# phasor.net
KiCad netlist of a schematic drawn in EAGLE
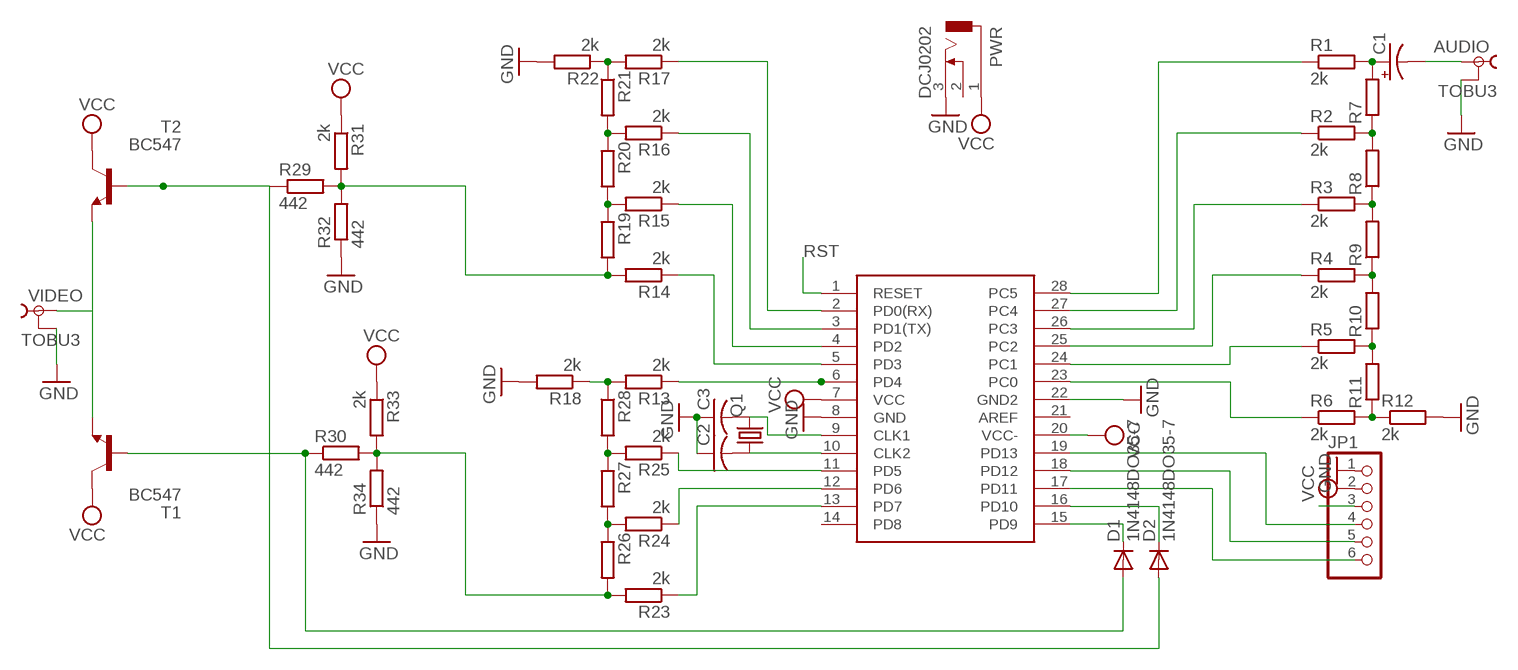
[diagram p0: schematic, sheet 1]

(export (version "E")
  (design (tool "Eeschema 10.0.6"))
  (components
    (comp (ref "AUDIO")
      (value "TOBU3")
      (footprint "eagle-import:TOBU3")
      (fields (field (name "MF") "FARNELL") (field (name "MPN") "TOBU 3"))
      (libsource (lib "eagle-import") (part "TOBU3"))
    )
    (comp (ref "C1")
      (value "CPOL-USB45181A")
      (footprint "eagle-import:B45181A")
      (libsource (lib "eagle-import") (part "CPOL-USB45181A"))
    )
    (comp (ref "C2")
      (value "C-US025-024X044")
      (footprint "eagle-import:C025-024X044")
      (libsource (lib "eagle-import") (part "C-US025-024X044"))
    )
    (comp (ref "C3")
      (value "C-US025-024X044")
      (footprint "eagle-import:C025-024X044")
      (libsource (lib "eagle-import") (part "C-US025-024X044"))
    )
    (comp (ref "D1")
      (value "1N4148DO35-7")
      (footprint "eagle-import:DO35-7")
      (libsource (lib "eagle-import") (part "1N4148DO35-7"))
    )
    (comp (ref "D2")
      (value "1N4148DO35-7")
      (footprint "eagle-import:DO35-7")
      (libsource (lib "eagle-import") (part "1N4148DO35-7"))
    )
    (comp (ref "JP1")
      (value "PINHD-1X6")
      (footprint "eagle-import:1X06")
      (libsource (lib "eagle-import") (part "PINHD-1X6"))
    )
    (comp (ref "PWR")
      (value "DCJ0202")
      (footprint "eagle-import:DCJ0202")
      (libsource (lib "eagle-import") (part "DCJ0202"))
    )
    (comp (ref "Q1")
      (value "CRYSTALHC49U70")
      (footprint "eagle-import:HC49U70")
      (libsource (lib "eagle-import") (part "CRYSTALHC49U70"))
    )
    (comp (ref "R1")
      (value "2k")
      (footprint "eagle-import:0207_10")
      (libsource (lib "eagle-import") (part "R-EU_0207/10"))
    )
    (comp (ref "R2")
      (value "2k")
      (footprint "eagle-import:0207_10")
      (libsource (lib "eagle-import") (part "R-EU_0207/10"))
    )
    (comp (ref "R3")
      (value "2k")
      (footprint "eagle-import:0207_10")
      (libsource (lib "eagle-import") (part "R-EU_0207/10"))
    )
    (comp (ref "R4")
      (value "2k")
      (footprint "eagle-import:0207_10")
      (libsource (lib "eagle-import") (part "R-EU_0207/10"))
    )
    (comp (ref "R5")
      (value "2k")
      (footprint "eagle-import:0207_10")
      (libsource (lib "eagle-import") (part "R-EU_0207/10"))
    )
    (comp (ref "R6")
      (value "2k")
      (footprint "eagle-import:0207_10")
      (libsource (lib "eagle-import") (part "R-EU_0207/10"))
    )
    (comp (ref "R7")
      (value "R-EU_0204/2V")
      (footprint "eagle-import:0204V")
      (libsource (lib "eagle-import") (part "R-EU_0204/2V"))
    )
    (comp (ref "R8")
      (value "R-EU_0204/2V")
      (footprint "eagle-import:0204V")
      (libsource (lib "eagle-import") (part "R-EU_0204/2V"))
    )
    (comp (ref "R9")
      (value "R-EU_0204/2V")
      (footprint "eagle-import:0204V")
      (libsource (lib "eagle-import") (part "R-EU_0204/2V"))
    )
    (comp (ref "R10")
      (value "R-EU_0204/2V")
      (footprint "eagle-import:0204V")
      (libsource (lib "eagle-import") (part "R-EU_0204/2V"))
    )
    (comp (ref "R11")
      (value "R-EU_0204/2V")
      (footprint "eagle-import:0204V")
      (libsource (lib "eagle-import") (part "R-EU_0204/2V"))
    )
    (comp (ref "R12")
      (value "2k")
      (footprint "eagle-import:0207_10")
      (libsource (lib "eagle-import") (part "R-EU_0207/10"))
    )
    (comp (ref "R13")
      (value "2k")
      (footprint "eagle-import:0207_10")
      (libsource (lib "eagle-import") (part "R-EU_0207/10"))
    )
    (comp (ref "R14")
      (value "2k")
      (footprint "eagle-import:0207_10")
      (libsource (lib "eagle-import") (part "R-EU_0207/10"))
    )
    (comp (ref "R15")
      (value "2k")
      (footprint "eagle-import:0207_10")
      (libsource (lib "eagle-import") (part "R-EU_0207/10"))
    )
    (comp (ref "R16")
      (value "2k")
      (footprint "eagle-import:0207_10")
      (libsource (lib "eagle-import") (part "R-EU_0207/10"))
    )
    (comp (ref "R17")
      (value "2k")
      (footprint "eagle-import:0207_10")
      (libsource (lib "eagle-import") (part "R-EU_0207/10"))
    )
    (comp (ref "R18")
      (value "2k")
      (footprint "eagle-import:0207_10")
      (libsource (lib "eagle-import") (part "R-EU_0207/10"))
    )
    (comp (ref "R19")
      (value "R-EU_0204/2V")
      (footprint "eagle-import:0204V")
      (libsource (lib "eagle-import") (part "R-EU_0204/2V"))
    )
    (comp (ref "R20")
      (value "R-EU_0204/2V")
      (footprint "eagle-import:0204V")
      (libsource (lib "eagle-import") (part "R-EU_0204/2V"))
    )
    (comp (ref "R21")
      (value "R-EU_0204/2V")
      (footprint "eagle-import:0204V")
      (libsource (lib "eagle-import") (part "R-EU_0204/2V"))
    )
    (comp (ref "R22")
      (value "2k")
      (footprint "eagle-import:0207_10")
      (libsource (lib "eagle-import") (part "R-EU_0207/10"))
    )
    (comp (ref "R23")
      (value "2k")
      (footprint "eagle-import:0207_10")
      (libsource (lib "eagle-import") (part "R-EU_0207/10"))
    )
    (comp (ref "R24")
      (value "2k")
      (footprint "eagle-import:0207_10")
      (libsource (lib "eagle-import") (part "R-EU_0207/10"))
    )
    (comp (ref "R25")
      (value "2k")
      (footprint "eagle-import:0207_10")
      (libsource (lib "eagle-import") (part "R-EU_0207/10"))
    )
    (comp (ref "R26")
      (value "R-EU_0204/2V")
      (footprint "eagle-import:0204V")
      (libsource (lib "eagle-import") (part "R-EU_0204/2V"))
    )
    (comp (ref "R27")
      (value "R-EU_0204/2V")
      (footprint "eagle-import:0204V")
      (libsource (lib "eagle-import") (part "R-EU_0204/2V"))
    )
    (comp (ref "R28")
      (value "R-EU_0204/2V")
      (footprint "eagle-import:0204V")
      (libsource (lib "eagle-import") (part "R-EU_0204/2V"))
    )
    (comp (ref "R29")
      (value "442")
      (footprint "eagle-import:0204_5")
      (libsource (lib "eagle-import") (part "R-EU_0204/5"))
    )
    (comp (ref "R30")
      (value "442")
      (footprint "eagle-import:0204V")
      (libsource (lib "eagle-import") (part "R-EU_0204/2V"))
    )
    (comp (ref "R31")
      (value "2k")
      (footprint "eagle-import:0207_10")
      (libsource (lib "eagle-import") (part "R-EU_0207/10"))
    )
    (comp (ref "R32")
      (value "442")
      (footprint "eagle-import:0204V")
      (libsource (lib "eagle-import") (part "R-EU_0204/2V"))
    )
    (comp (ref "R33")
      (value "2k")
      (footprint "eagle-import:0207_10")
      (libsource (lib "eagle-import") (part "R-EU_0207/10"))
    )
    (comp (ref "R34")
      (value "442")
      (footprint "eagle-import:0204V")
      (libsource (lib "eagle-import") (part "R-EU_0204/2V"))
    )
    (comp (ref "T1")
      (value "BC547")
      (footprint "eagle-import:TO92")
      (libsource (lib "eagle-import") (part "BC547"))
    )
    (comp (ref "T2")
      (value "BC547")
      (footprint "eagle-import:TO92")
      (libsource (lib "eagle-import") (part "BC547"))
    )
    (comp (ref "U$1")
      (value "328P")
      (footprint "eagle-import:DIL28-3")
      (libsource (lib "eagle-import") (part "328P"))
    )
    (comp (ref "VIDEO")
      (value "TOBU3")
      (footprint "eagle-import:TOBU3")
      (fields (field (name "MF") "FARNELL") (field (name "MPN") "TOBU 3"))
      (libsource (lib "eagle-import") (part "TOBU3"))
    )
  )
  (nets
    (net (code "1") (name "/RST") (class "Default")
      (node (ref "JP1") (pin "3") (pinfunction "3_3") (pintype "passive"))
      (node (ref "U$1") (pin "1") (pinfunction "RESET_1") (pintype "bidirectional"))
    )
    (net (code "2") (name "GND") (class "Default")
      (node (ref "AUDIO") (pin "2") (pinfunction "2_2") (pintype "passive"))
      (node (ref "AUDIO") (pin "2@1") (pinfunction "2_2@1") (pintype "passive"))
      (node (ref "AUDIO") (pin "2@2") (pinfunction "2_2@2") (pintype "passive"))
      (node (ref "C2") (pin "1") (pinfunction "1_1") (pintype "passive"))
      (node (ref "C3") (pin "1") (pinfunction "1_1") (pintype "passive"))
      (node (ref "JP1") (pin "1") (pinfunction "1_1") (pintype "passive"))
      (node (ref "PWR") (pin "3") (pinfunction "3_3") (pintype "passive"))
      (node (ref "R12") (pin "2") (pinfunction "2_2") (pintype "passive"))
      (node (ref "R18") (pin "2") (pinfunction "2_2") (pintype "passive"))
      (node (ref "R22") (pin "2") (pinfunction "2_2") (pintype "passive"))
      (node (ref "R32") (pin "1") (pinfunction "1_1") (pintype "passive"))
      (node (ref "R34") (pin "1") (pinfunction "1_1") (pintype "passive"))
      (node (ref "U$1") (pin "22") (pinfunction "GND2_22") (pintype "bidirectional"))
      (node (ref "U$1") (pin "8") (pinfunction "GND_8") (pintype "bidirectional"))
      (node (ref "VIDEO") (pin "2") (pinfunction "2_2") (pintype "passive"))
      (node (ref "VIDEO") (pin "2@1") (pinfunction "2_2@1") (pintype "passive"))
      (node (ref "VIDEO") (pin "2@2") (pinfunction "2_2@2") (pintype "passive"))
    )
    (net (code "3") (name "Net-(AUDIO-Pad1)") (class "Default")
      (node (ref "AUDIO") (pin "1") (pinfunction "1_1") (pintype "passive"))
      (node (ref "C1") (pin "-") (pinfunction "-_-") (pintype "passive"))
    )
    (net (code "4") (name "Net-(C1-Pad+)") (class "Default")
      (node (ref "C1") (pin "+") (pinfunction "+_+") (pintype "passive"))
      (node (ref "R1") (pin "2") (pinfunction "2_2") (pintype "passive"))
      (node (ref "R7") (pin "2") (pinfunction "2_2") (pintype "passive"))
    )
    (net (code "5") (name "Net-(R2-Pad2)") (class "Default")
      (node (ref "R2") (pin "2") (pinfunction "2_2") (pintype "passive"))
      (node (ref "R7") (pin "1") (pinfunction "1_1") (pintype "passive"))
      (node (ref "R8") (pin "2") (pinfunction "2_2") (pintype "passive"))
    )
    (net (code "6") (name "Net-(R3-Pad2)") (class "Default")
      (node (ref "R3") (pin "2") (pinfunction "2_2") (pintype "passive"))
      (node (ref "R8") (pin "1") (pinfunction "1_1") (pintype "passive"))
      (node (ref "R9") (pin "2") (pinfunction "2_2") (pintype "passive"))
    )
    (net (code "7") (name "Net-(R10-Pad1)") (class "Default")
      (node (ref "R10") (pin "1") (pinfunction "1_1") (pintype "passive"))
      (node (ref "R11") (pin "2") (pinfunction "2_2") (pintype "passive"))
      (node (ref "R5") (pin "2") (pinfunction "2_2") (pintype "passive"))
    )
    (net (code "8") (name "Net-(R10-Pad2)") (class "Default")
      (node (ref "R10") (pin "2") (pinfunction "2_2") (pintype "passive"))
      (node (ref "R4") (pin "2") (pinfunction "2_2") (pintype "passive"))
      (node (ref "R9") (pin "1") (pinfunction "1_1") (pintype "passive"))
    )
    (net (code "9") (name "Net-(R11-Pad1)") (class "Default")
      (node (ref "R11") (pin "1") (pinfunction "1_1") (pintype "passive"))
      (node (ref "R12") (pin "1") (pinfunction "1_1") (pintype "passive"))
      (node (ref "R6") (pin "2") (pinfunction "2_2") (pintype "passive"))
    )
    (net (code "10") (name "Net-(R13-Pad2)") (class "Default")
      (node (ref "R13") (pin "2") (pinfunction "2_2") (pintype "passive"))
      (node (ref "R18") (pin "1") (pinfunction "1_1") (pintype "passive"))
      (node (ref "R28") (pin "1") (pinfunction "1_1") (pintype "passive"))
    )
    (net (code "11") (name "Net-(R14-Pad2)") (class "Default")
      (node (ref "R14") (pin "2") (pinfunction "2_2") (pintype "passive"))
      (node (ref "R19") (pin "2") (pinfunction "2_2") (pintype "passive"))
      (node (ref "R29") (pin "2") (pinfunction "2_2") (pintype "passive"))
      (node (ref "R31") (pin "2") (pinfunction "2_2") (pintype "passive"))
      (node (ref "R32") (pin "2") (pinfunction "2_2") (pintype "passive"))
    )
    (net (code "12") (name "Net-(R15-Pad2)") (class "Default")
      (node (ref "R15") (pin "2") (pinfunction "2_2") (pintype "passive"))
      (node (ref "R19") (pin "1") (pinfunction "1_1") (pintype "passive"))
      (node (ref "R20") (pin "2") (pinfunction "2_2") (pintype "passive"))
    )
    (net (code "13") (name "Net-(R16-Pad2)") (class "Default")
      (node (ref "R16") (pin "2") (pinfunction "2_2") (pintype "passive"))
      (node (ref "R20") (pin "1") (pinfunction "1_1") (pintype "passive"))
      (node (ref "R21") (pin "2") (pinfunction "2_2") (pintype "passive"))
    )
    (net (code "14") (name "Net-(R17-Pad2)") (class "Default")
      (node (ref "R17") (pin "2") (pinfunction "2_2") (pintype "passive"))
      (node (ref "R21") (pin "1") (pinfunction "1_1") (pintype "passive"))
      (node (ref "R22") (pin "1") (pinfunction "1_1") (pintype "passive"))
    )
    (net (code "15") (name "Net-(R23-Pad2)") (class "Default")
      (node (ref "R23") (pin "2") (pinfunction "2_2") (pintype "passive"))
      (node (ref "R26") (pin "2") (pinfunction "2_2") (pintype "passive"))
      (node (ref "R30") (pin "2") (pinfunction "2_2") (pintype "passive"))
      (node (ref "R33") (pin "2") (pinfunction "2_2") (pintype "passive"))
      (node (ref "R34") (pin "2") (pinfunction "2_2") (pintype "passive"))
    )
    (net (code "16") (name "Net-(R24-Pad2)") (class "Default")
      (node (ref "R24") (pin "2") (pinfunction "2_2") (pintype "passive"))
      (node (ref "R26") (pin "1") (pinfunction "1_1") (pintype "passive"))
      (node (ref "R27") (pin "2") (pinfunction "2_2") (pintype "passive"))
    )
    (net (code "17") (name "Net-(R25-Pad2)") (class "Default")
      (node (ref "R25") (pin "2") (pinfunction "2_2") (pintype "passive"))
      (node (ref "R27") (pin "1") (pinfunction "1_1") (pintype "passive"))
      (node (ref "R28") (pin "2") (pinfunction "2_2") (pintype "passive"))
    )
    (net (code "18") (name "Net-(T1-B)") (class "Default")
      (node (ref "D1") (pin "A") (pinfunction "A_A") (pintype "passive"))
      (node (ref "R30") (pin "1") (pinfunction "1_1") (pintype "passive"))
      (node (ref "T1") (pin "2") (pinfunction "B_2") (pintype "passive"))
    )
    (net (code "19") (name "Net-(T1-E)") (class "Default")
      (node (ref "T1") (pin "1") (pinfunction "E_1") (pintype "passive"))
      (node (ref "T2") (pin "1") (pinfunction "E_1") (pintype "passive"))
      (node (ref "VIDEO") (pin "1") (pinfunction "1_1") (pintype "passive"))
    )
    (net (code "20") (name "Net-(T2-B)") (class "Default")
      (node (ref "D2") (pin "A") (pinfunction "A_A") (pintype "passive"))
      (node (ref "R29") (pin "1") (pinfunction "1_1") (pintype "passive"))
      (node (ref "T2") (pin "2") (pinfunction "B_2") (pintype "passive"))
    )
    (net (code "21") (name "Net-(U$1-CLK1)") (class "Default")
      (node (ref "C3") (pin "2") (pinfunction "2_2") (pintype "passive"))
      (node (ref "Q1") (pin "2") (pinfunction "2_2") (pintype "passive"))
      (node (ref "U$1") (pin "9") (pinfunction "CLK1_9") (pintype "bidirectional"))
    )
    (net (code "22") (name "Net-(U$1-CLK2)") (class "Default")
      (node (ref "C2") (pin "2") (pinfunction "2_2") (pintype "passive"))
      (node (ref "Q1") (pin "1") (pinfunction "1_1") (pintype "passive"))
      (node (ref "U$1") (pin "10") (pinfunction "CLK2_10") (pintype "bidirectional"))
    )
    (net (code "23") (name "Net-(U$1-PC0)") (class "Default")
      (node (ref "R6") (pin "1") (pinfunction "1_1") (pintype "passive"))
      (node (ref "U$1") (pin "23") (pinfunction "PC0_23") (pintype "bidirectional"))
    )
    (net (code "24") (name "Net-(U$1-PC1)") (class "Default")
      (node (ref "R5") (pin "1") (pinfunction "1_1") (pintype "passive"))
      (node (ref "U$1") (pin "24") (pinfunction "PC1_24") (pintype "bidirectional"))
    )
    (net (code "25") (name "Net-(U$1-PC2)") (class "Default")
      (node (ref "R4") (pin "1") (pinfunction "1_1") (pintype "passive"))
      (node (ref "U$1") (pin "25") (pinfunction "PC2_25") (pintype "bidirectional"))
    )
    (net (code "26") (name "Net-(U$1-PC3)") (class "Default")
      (node (ref "R3") (pin "1") (pinfunction "1_1") (pintype "passive"))
      (node (ref "U$1") (pin "26") (pinfunction "PC3_26") (pintype "bidirectional"))
    )
    (net (code "27") (name "Net-(U$1-PC4)") (class "Default")
      (node (ref "R2") (pin "1") (pinfunction "1_1") (pintype "passive"))
      (node (ref "U$1") (pin "27") (pinfunction "PC4_27") (pintype "bidirectional"))
    )
    (net (code "28") (name "Net-(U$1-PC5)") (class "Default")
      (node (ref "R1") (pin "1") (pinfunction "1_1") (pintype "passive"))
      (node (ref "U$1") (pin "28") (pinfunction "PC5_28") (pintype "bidirectional"))
    )
    (net (code "29") (name "Net-(U$1-PD0(RX))") (class "Default")
      (node (ref "R17") (pin "1") (pinfunction "1_1") (pintype "passive"))
      (node (ref "U$1") (pin "2") (pinfunction "PD0(RX)_2") (pintype "bidirectional"))
    )
    (net (code "30") (name "Net-(U$1-PD1(TX))") (class "Default")
      (node (ref "R16") (pin "1") (pinfunction "1_1") (pintype "passive"))
      (node (ref "U$1") (pin "3") (pinfunction "PD1(TX)_3") (pintype "bidirectional"))
    )
    (net (code "31") (name "Net-(U$1-PD2)") (class "Default")
      (node (ref "R15") (pin "1") (pinfunction "1_1") (pintype "passive"))
      (node (ref "U$1") (pin "4") (pinfunction "PD2_4") (pintype "bidirectional"))
    )
    (net (code "32") (name "Net-(U$1-PD3)") (class "Default")
      (node (ref "R14") (pin "1") (pinfunction "1_1") (pintype "passive"))
      (node (ref "U$1") (pin "5") (pinfunction "PD3_5") (pintype "bidirectional"))
    )
    (net (code "33") (name "Net-(U$1-PD4)") (class "Default")
      (node (ref "R13") (pin "1") (pinfunction "1_1") (pintype "passive"))
      (node (ref "U$1") (pin "6") (pinfunction "PD4_6") (pintype "bidirectional"))
    )
    (net (code "34") (name "Net-(U$1-PD5)") (class "Default")
      (node (ref "R25") (pin "1") (pinfunction "1_1") (pintype "passive"))
      (node (ref "U$1") (pin "11") (pinfunction "PD5_11") (pintype "bidirectional"))
    )
    (net (code "35") (name "Net-(U$1-PD6)") (class "Default")
      (node (ref "R24") (pin "1") (pinfunction "1_1") (pintype "passive"))
      (node (ref "U$1") (pin "12") (pinfunction "PD6_12") (pintype "bidirectional"))
    )
    (net (code "36") (name "Net-(U$1-PD7)") (class "Default")
      (node (ref "R23") (pin "1") (pinfunction "1_1") (pintype "passive"))
      (node (ref "U$1") (pin "13") (pinfunction "PD7_13") (pintype "bidirectional"))
    )
    (net (code "37") (name "Net-(U$1-PD9)") (class "Default")
      (node (ref "D1") (pin "C") (pinfunction "C_C") (pintype "passive"))
      (node (ref "U$1") (pin "15") (pinfunction "PD9_15") (pintype "bidirectional"))
    )
    (net (code "38") (name "Net-(U$1-PD10)") (class "Default")
      (node (ref "D2") (pin "C") (pinfunction "C_C") (pintype "passive"))
      (node (ref "U$1") (pin "16") (pinfunction "PD10_16") (pintype "bidirectional"))
    )
    (net (code "39") (name "Net-(U$1-PD11)") (class "Default")
      (node (ref "JP1") (pin "6") (pinfunction "6_6") (pintype "passive"))
      (node (ref "U$1") (pin "17") (pinfunction "PD11_17") (pintype "bidirectional"))
    )
    (net (code "40") (name "Net-(U$1-PD12)") (class "Default")
      (node (ref "JP1") (pin "5") (pinfunction "5_5") (pintype "passive"))
      (node (ref "U$1") (pin "18") (pinfunction "PD12_18") (pintype "bidirectional"))
    )
    (net (code "41") (name "Net-(U$1-PD13)") (class "Default")
      (node (ref "JP1") (pin "4") (pinfunction "4_4") (pintype "passive"))
      (node (ref "U$1") (pin "19") (pinfunction "PD13_19") (pintype "bidirectional"))
    )
    (net (code "42") (name "VCC") (class "Default")
      (node (ref "JP1") (pin "2") (pinfunction "2_2") (pintype "passive"))
      (node (ref "PWR") (pin "1") (pinfunction "1_1") (pintype "passive"))
      (node (ref "R31") (pin "1") (pinfunction "1_1") (pintype "passive"))
      (node (ref "R33") (pin "1") (pinfunction "1_1") (pintype "passive"))
      (node (ref "T1") (pin "3") (pinfunction "C_3") (pintype "passive"))
      (node (ref "T2") (pin "3") (pinfunction "C_3") (pintype "passive"))
      (node (ref "U$1") (pin "20") (pinfunction "VCC-_20") (pintype "bidirectional"))
      (node (ref "U$1") (pin "7") (pinfunction "VCC_7") (pintype "bidirectional"))
    )
    (net (code "43") (name "unconnected-(PWR-Pad2)") (class "Default")
      (node (ref "PWR") (pin "2") (pinfunction "2_2") (pintype "passive"))
    )
    (net (code "44") (name "unconnected-(U$1-AREF-Pad21)") (class "Default")
      (node (ref "U$1") (pin "21") (pinfunction "AREF_21") (pintype "bidirectional"))
    )
    (net (code "45") (name "unconnected-(U$1-PD8-Pad14)") (class "Default")
      (node (ref "U$1") (pin "14") (pinfunction "PD8_14") (pintype "bidirectional"))
    )
  )
)
